# AD_2.net
KiCad netlist of a schematic drawn in Altium Designer
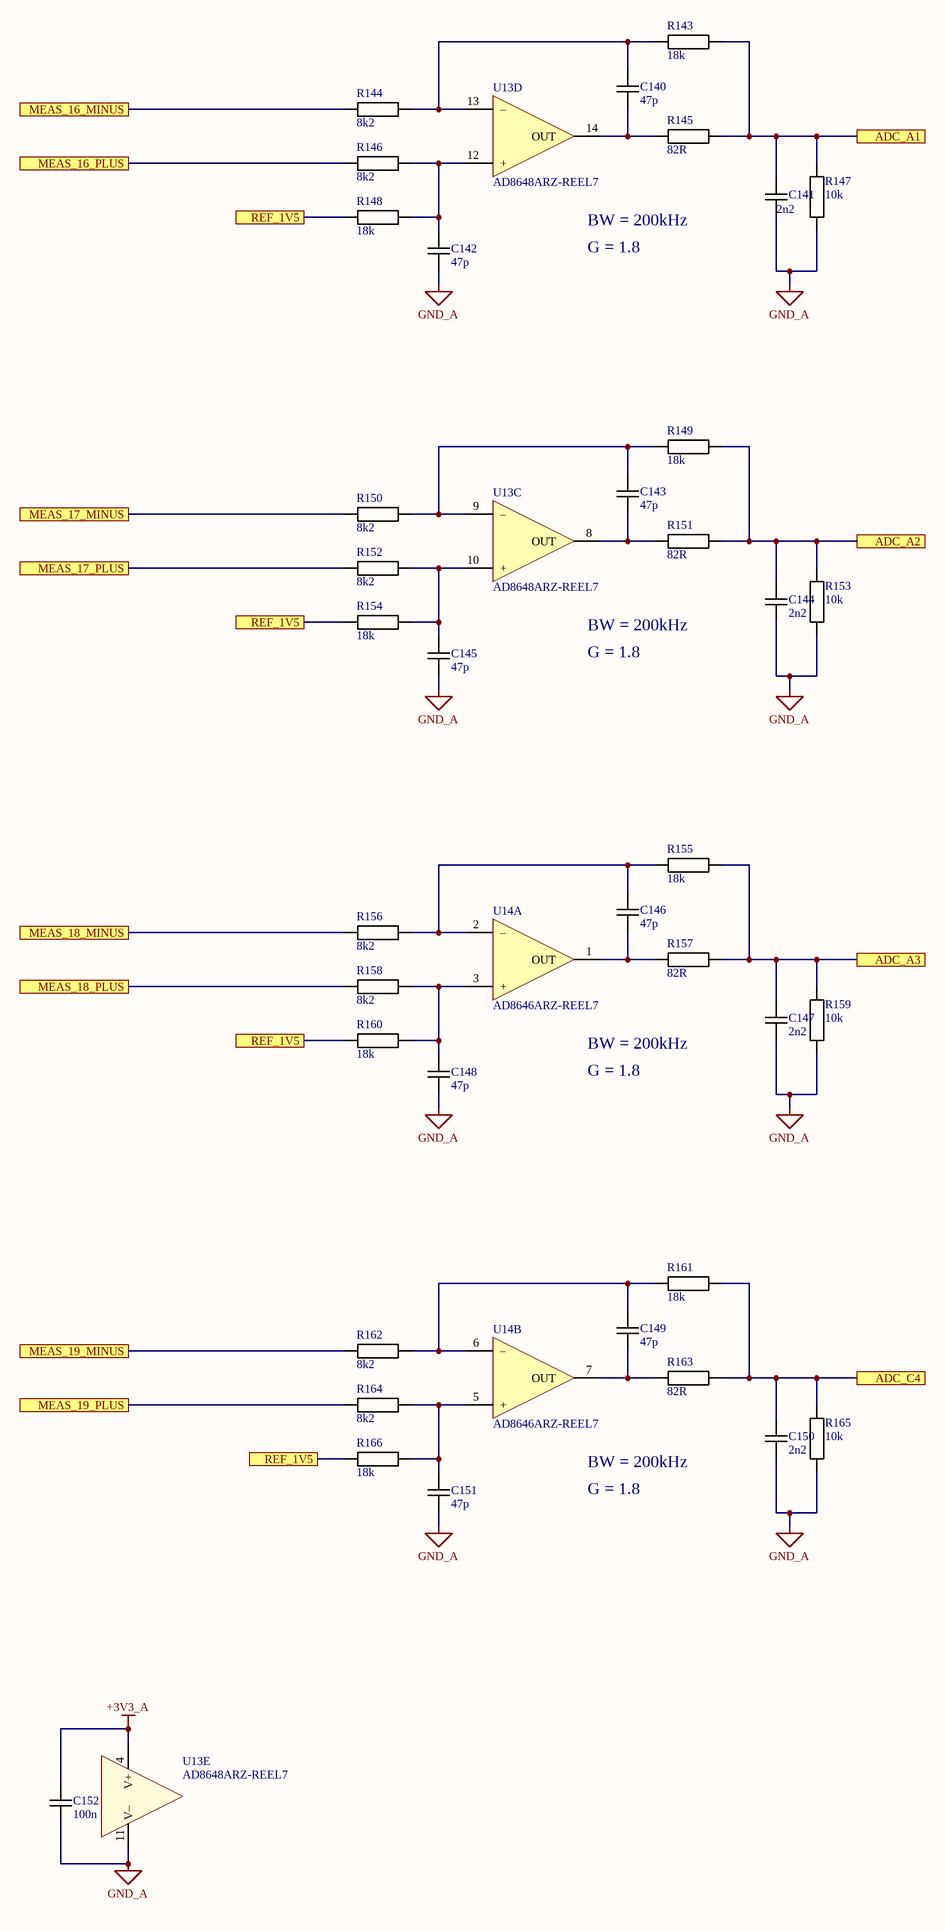
[diagram p0: AD_2.SchDoc]

(export (version "E")
  (design (tool "Eeschema 10.0.6"))
  (components
    (comp (ref "C140")
      (value "47p")
      (footprint "CAPACITOR 1608 REFLOW")
      (description "Capacitor X7R 10% 50V 1608(0603)")
      (libsource (lib "Capacitor") (part "Capacitor"))
    )
    (comp (ref "C141")
      (value "2n2")
      (footprint "CAPACITOR 1608 REFLOW")
      (description "Capacitor X7R 10% 50V 1608(0603)")
      (libsource (lib "Capacitor") (part "Capacitor"))
    )
    (comp (ref "C142")
      (value "47p")
      (footprint "CAPACITOR 1608 REFLOW")
      (description "Capacitor X7R 10% 50V 1608(0603)")
      (libsource (lib "Capacitor") (part "Capacitor"))
    )
    (comp (ref "C143")
      (value "47p")
      (footprint "CAPACITOR 1608 REFLOW")
      (description "Capacitor X7R 10% 50V 1608(0603)")
      (libsource (lib "Capacitor") (part "Capacitor"))
    )
    (comp (ref "C144")
      (value "2n2")
      (footprint "CAPACITOR 1608 REFLOW")
      (description "Capacitor X7R 10% 50V 1608(0603)")
      (libsource (lib "Capacitor") (part "Capacitor"))
    )
    (comp (ref "C145")
      (value "47p")
      (footprint "CAPACITOR 1608 REFLOW")
      (description "Capacitor X7R 10% 50V 1608(0603)")
      (libsource (lib "Capacitor") (part "Capacitor"))
    )
    (comp (ref "C146")
      (value "47p")
      (footprint "CAPACITOR 1608 REFLOW")
      (description "Capacitor X7R 10% 50V 1608(0603)")
      (libsource (lib "Capacitor") (part "Capacitor"))
    )
    (comp (ref "C147")
      (value "2n2")
      (footprint "CAPACITOR 1608 REFLOW")
      (description "Capacitor X7R 10% 50V 1608(0603)")
      (libsource (lib "Capacitor") (part "Capacitor"))
    )
    (comp (ref "C148")
      (value "47p")
      (footprint "CAPACITOR 1608 REFLOW")
      (description "Capacitor X7R 10% 50V 1608(0603)")
      (libsource (lib "Capacitor") (part "Capacitor"))
    )
    (comp (ref "C149")
      (value "47p")
      (footprint "CAPACITOR 1608 REFLOW")
      (description "Capacitor X7R 10% 50V 1608(0603)")
      (libsource (lib "Capacitor") (part "Capacitor"))
    )
    (comp (ref "C150")
      (value "2n2")
      (footprint "CAPACITOR 1608 REFLOW")
      (description "Capacitor X7R 10% 50V 1608(0603)")
      (libsource (lib "Capacitor") (part "Capacitor"))
    )
    (comp (ref "C151")
      (value "47p")
      (footprint "CAPACITOR 1608 REFLOW")
      (description "Capacitor X7R 10% 50V 1608(0603)")
      (libsource (lib "Capacitor") (part "Capacitor"))
    )
    (comp (ref "C152")
      (value "100n")
      (footprint "CAPACITOR 1608 REFLOW")
      (description "Capacitor X7R 10% 50V 1608(0603)")
      (libsource (lib "Capacitor") (part "Capacitor"))
    )
    (comp (ref "R143")
      (value "18k")
      (footprint "RESISTOR 1608 REFLOW")
      (description "Resistor 1% 50V 100mW 1608(0603)")
      (libsource (lib "Resistor") (part "Resistor"))
    )
    (comp (ref "R144")
      (value "8k2")
      (footprint "RESISTOR 1608 REFLOW")
      (description "Resistor 1% 50V 100mW 1608(0603)")
      (libsource (lib "Resistor") (part "Resistor"))
    )
    (comp (ref "R145")
      (value "82R")
      (footprint "RESISTOR 1608 REFLOW")
      (description "Resistor 1% 50V 100mW 1608(0603)")
      (libsource (lib "Resistor") (part "Resistor"))
    )
    (comp (ref "R146")
      (value "8k2")
      (footprint "RESISTOR 1608 REFLOW")
      (description "Resistor 1% 50V 100mW 1608(0603)")
      (libsource (lib "Resistor") (part "Resistor"))
    )
    (comp (ref "R147")
      (value "10k")
      (footprint "RESISTOR 1608 REFLOW")
      (description "Resistor 1% 50V 100mW 1608(0603)")
      (libsource (lib "Resistor") (part "Resistor"))
    )
    (comp (ref "R148")
      (value "18k")
      (footprint "RESISTOR 1608 REFLOW")
      (description "Resistor 1% 50V 100mW 1608(0603)")
      (libsource (lib "Resistor") (part "Resistor"))
    )
    (comp (ref "R149")
      (value "18k")
      (footprint "RESISTOR 1608 REFLOW")
      (description "Resistor 1% 50V 100mW 1608(0603)")
      (libsource (lib "Resistor") (part "Resistor"))
    )
    (comp (ref "R150")
      (value "8k2")
      (footprint "RESISTOR 1608 REFLOW")
      (description "Resistor 1% 50V 100mW 1608(0603)")
      (libsource (lib "Resistor") (part "Resistor"))
    )
    (comp (ref "R151")
      (value "82R")
      (footprint "RESISTOR 1608 REFLOW")
      (description "Resistor 1% 50V 100mW 1608(0603)")
      (libsource (lib "Resistor") (part "Resistor"))
    )
    (comp (ref "R152")
      (value "8k2")
      (footprint "RESISTOR 1608 REFLOW")
      (description "Resistor 1% 50V 100mW 1608(0603)")
      (libsource (lib "Resistor") (part "Resistor"))
    )
    (comp (ref "R153")
      (value "10k")
      (footprint "RESISTOR 1608 REFLOW")
      (description "Resistor 1% 50V 100mW 1608(0603)")
      (libsource (lib "Resistor") (part "Resistor"))
    )
    (comp (ref "R154")
      (value "18k")
      (footprint "RESISTOR 1608 REFLOW")
      (description "Resistor 1% 50V 100mW 1608(0603)")
      (libsource (lib "Resistor") (part "Resistor"))
    )
    (comp (ref "R155")
      (value "18k")
      (footprint "RESISTOR 1608 REFLOW")
      (description "Resistor 1% 50V 100mW 1608(0603)")
      (libsource (lib "Resistor") (part "Resistor"))
    )
    (comp (ref "R156")
      (value "8k2")
      (footprint "RESISTOR 1608 REFLOW")
      (description "Resistor 1% 50V 100mW 1608(0603)")
      (libsource (lib "Resistor") (part "Resistor"))
    )
    (comp (ref "R157")
      (value "82R")
      (footprint "RESISTOR 1608 REFLOW")
      (description "Resistor 1% 50V 100mW 1608(0603)")
      (libsource (lib "Resistor") (part "Resistor"))
    )
    (comp (ref "R158")
      (value "8k2")
      (footprint "RESISTOR 1608 REFLOW")
      (description "Resistor 1% 50V 100mW 1608(0603)")
      (libsource (lib "Resistor") (part "Resistor"))
    )
    (comp (ref "R159")
      (value "10k")
      (footprint "RESISTOR 1608 REFLOW")
      (description "Resistor 1% 50V 100mW 1608(0603)")
      (libsource (lib "Resistor") (part "Resistor"))
    )
    (comp (ref "R160")
      (value "18k")
      (footprint "RESISTOR 1608 REFLOW")
      (description "Resistor 1% 50V 100mW 1608(0603)")
      (libsource (lib "Resistor") (part "Resistor"))
    )
    (comp (ref "R161")
      (value "18k")
      (footprint "RESISTOR 1608 REFLOW")
      (description "Resistor 1% 50V 100mW 1608(0603)")
      (libsource (lib "Resistor") (part "Resistor"))
    )
    (comp (ref "R162")
      (value "8k2")
      (footprint "RESISTOR 1608 REFLOW")
      (description "Resistor 1% 50V 100mW 1608(0603)")
      (libsource (lib "Resistor") (part "Resistor"))
    )
    (comp (ref "R163")
      (value "82R")
      (footprint "RESISTOR 1608 REFLOW")
      (description "Resistor 1% 50V 100mW 1608(0603)")
      (libsource (lib "Resistor") (part "Resistor"))
    )
    (comp (ref "R164")
      (value "8k2")
      (footprint "RESISTOR 1608 REFLOW")
      (description "Resistor 1% 50V 100mW 1608(0603)")
      (libsource (lib "Resistor") (part "Resistor"))
    )
    (comp (ref "R165")
      (value "10k")
      (footprint "RESISTOR 1608 REFLOW")
      (description "Resistor 1% 50V 100mW 1608(0603)")
      (libsource (lib "Resistor") (part "Resistor"))
    )
    (comp (ref "R166")
      (value "18k")
      (footprint "RESISTOR 1608 REFLOW")
      (description "Resistor 1% 50V 100mW 1608(0603)")
      (libsource (lib "Resistor") (part "Resistor"))
    )
    (comp (ref "U13")
      (value "AD8648ARZ-REEL7")
      (footprint "SO14 P1.27 C4.0X8.8 H1.75")
      (description "Generic quad OPA 14 pins")
      (fields (field (name "MANUFACTURER") "Analog Device"))
      (libsource (lib "Amplifier") (part "OPA QUAD"))
    )
    (comp (ref "U14")
      (value "AD8646ARZ-REEL7")
      (footprint "SO8 P1.27 C4.0X5.0 H1.75")
      (description "Generic dual OPA 8 pins")
      (fields (field (name "MANUFACTURER") "Analog Devices"))
      (libsource (lib "Amplifier") (part "OPA DUAL"))
    )
  )
  (nets
    (net (code "1") (name "+3V3_A") (class "Default")
      (node (ref "C152") (pin "2") (pinfunction "2_2") (pintype "passive"))
      (node (ref "U13") (pin "4") (pinfunction "V+_4") (pintype "passive"))
    )
    (net (code "2") (name "/ADC_A1") (class "Default")
      (node (ref "C141") (pin "2") (pinfunction "2_2") (pintype "passive"))
      (node (ref "R143") (pin "2") (pinfunction "2_2") (pintype "passive"))
      (node (ref "R145") (pin "2") (pinfunction "2_2") (pintype "passive"))
      (node (ref "R147") (pin "1") (pinfunction "1_1") (pintype "passive"))
    )
    (net (code "3") (name "/ADC_A2") (class "Default")
      (node (ref "C144") (pin "2") (pinfunction "2_2") (pintype "passive"))
      (node (ref "R149") (pin "2") (pinfunction "2_2") (pintype "passive"))
      (node (ref "R151") (pin "2") (pinfunction "2_2") (pintype "passive"))
      (node (ref "R153") (pin "1") (pinfunction "1_1") (pintype "passive"))
    )
    (net (code "4") (name "/ADC_A3") (class "Default")
      (node (ref "C147") (pin "2") (pinfunction "2_2") (pintype "passive"))
      (node (ref "R155") (pin "2") (pinfunction "2_2") (pintype "passive"))
      (node (ref "R157") (pin "2") (pinfunction "2_2") (pintype "passive"))
      (node (ref "R159") (pin "1") (pinfunction "1_1") (pintype "passive"))
    )
    (net (code "5") (name "/ADC_C4") (class "Default")
      (node (ref "C150") (pin "2") (pinfunction "2_2") (pintype "passive"))
      (node (ref "R161") (pin "2") (pinfunction "2_2") (pintype "passive"))
      (node (ref "R163") (pin "2") (pinfunction "2_2") (pintype "passive"))
      (node (ref "R165") (pin "1") (pinfunction "1_1") (pintype "passive"))
    )
    (net (code "6") (name "/MEAS_16_MINUS") (class "Default")
      (node (ref "R144") (pin "1") (pinfunction "1_1") (pintype "passive"))
    )
    (net (code "7") (name "/MEAS_16_PLUS") (class "Default")
      (node (ref "R146") (pin "1") (pinfunction "1_1") (pintype "passive"))
    )
    (net (code "8") (name "/MEAS_17_MINUS") (class "Default")
      (node (ref "R150") (pin "1") (pinfunction "1_1") (pintype "passive"))
    )
    (net (code "9") (name "/MEAS_17_PLUS") (class "Default")
      (node (ref "R152") (pin "1") (pinfunction "1_1") (pintype "passive"))
    )
    (net (code "10") (name "/MEAS_18_MINUS") (class "Default")
      (node (ref "R156") (pin "1") (pinfunction "1_1") (pintype "passive"))
    )
    (net (code "11") (name "/MEAS_18_PLUS") (class "Default")
      (node (ref "R158") (pin "1") (pinfunction "1_1") (pintype "passive"))
    )
    (net (code "12") (name "/MEAS_19_MINUS") (class "Default")
      (node (ref "R162") (pin "1") (pinfunction "1_1") (pintype "passive"))
    )
    (net (code "13") (name "/MEAS_19_PLUS") (class "Default")
      (node (ref "R164") (pin "1") (pinfunction "1_1") (pintype "passive"))
    )
    (net (code "14") (name "/REF_1V5") (class "Default")
      (node (ref "R148") (pin "2") (pinfunction "2_2") (pintype "passive"))
      (node (ref "R154") (pin "2") (pinfunction "2_2") (pintype "passive"))
      (node (ref "R160") (pin "2") (pinfunction "2_2") (pintype "passive"))
      (node (ref "R166") (pin "2") (pinfunction "2_2") (pintype "passive"))
    )
    (net (code "15") (name "GND_A") (class "Default")
      (node (ref "C141") (pin "1") (pinfunction "1_1") (pintype "passive"))
      (node (ref "C142") (pin "1") (pinfunction "1_1") (pintype "passive"))
      (node (ref "C144") (pin "1") (pinfunction "1_1") (pintype "passive"))
      (node (ref "C145") (pin "1") (pinfunction "1_1") (pintype "passive"))
      (node (ref "C147") (pin "1") (pinfunction "1_1") (pintype "passive"))
      (node (ref "C148") (pin "1") (pinfunction "1_1") (pintype "passive"))
      (node (ref "C150") (pin "1") (pinfunction "1_1") (pintype "passive"))
      (node (ref "C151") (pin "1") (pinfunction "1_1") (pintype "passive"))
      (node (ref "C152") (pin "1") (pinfunction "1_1") (pintype "passive"))
      (node (ref "R147") (pin "2") (pinfunction "2_2") (pintype "passive"))
      (node (ref "R153") (pin "2") (pinfunction "2_2") (pintype "passive"))
      (node (ref "R159") (pin "2") (pinfunction "2_2") (pintype "passive"))
      (node (ref "R165") (pin "2") (pinfunction "2_2") (pintype "passive"))
      (node (ref "U13") (pin "11") (pinfunction "V–_11") (pintype "passive"))
    )
    (net (code "16") (name "Net-(U13C-+)") (class "Default")
      (node (ref "C145") (pin "2") (pinfunction "2_2") (pintype "passive"))
      (node (ref "R152") (pin "2") (pinfunction "2_2") (pintype "passive"))
      (node (ref "R154") (pin "1") (pinfunction "1_1") (pintype "passive"))
      (node (ref "U13") (pin "10") (pinfunction "+_10") (pintype "passive"))
    )
    (net (code "17") (name "Net-(U13C-OUT)") (class "Default")
      (node (ref "C143") (pin "1") (pinfunction "1_1") (pintype "passive"))
      (node (ref "R151") (pin "1") (pinfunction "1_1") (pintype "passive"))
      (node (ref "U13") (pin "8") (pinfunction "OUT_8") (pintype "passive"))
    )
    (net (code "18") (name "Net-(U13C-–)") (class "Default")
      (node (ref "C143") (pin "2") (pinfunction "2_2") (pintype "passive"))
      (node (ref "R149") (pin "1") (pinfunction "1_1") (pintype "passive"))
      (node (ref "R150") (pin "2") (pinfunction "2_2") (pintype "passive"))
      (node (ref "U13") (pin "9") (pinfunction "–_9") (pintype "passive"))
    )
    (net (code "19") (name "Net-(U13D-+)") (class "Default")
      (node (ref "C142") (pin "2") (pinfunction "2_2") (pintype "passive"))
      (node (ref "R146") (pin "2") (pinfunction "2_2") (pintype "passive"))
      (node (ref "R148") (pin "1") (pinfunction "1_1") (pintype "passive"))
      (node (ref "U13") (pin "12") (pinfunction "+_12") (pintype "passive"))
    )
    (net (code "20") (name "Net-(U13D-OUT)") (class "Default")
      (node (ref "C140") (pin "1") (pinfunction "1_1") (pintype "passive"))
      (node (ref "R145") (pin "1") (pinfunction "1_1") (pintype "passive"))
      (node (ref "U13") (pin "14") (pinfunction "OUT_14") (pintype "passive"))
    )
    (net (code "21") (name "Net-(U13D-–)") (class "Default")
      (node (ref "C140") (pin "2") (pinfunction "2_2") (pintype "passive"))
      (node (ref "R143") (pin "1") (pinfunction "1_1") (pintype "passive"))
      (node (ref "R144") (pin "2") (pinfunction "2_2") (pintype "passive"))
      (node (ref "U13") (pin "13") (pinfunction "–_13") (pintype "passive"))
    )
    (net (code "22") (name "Net-(U14A-+)") (class "Default")
      (node (ref "C148") (pin "2") (pinfunction "2_2") (pintype "passive"))
      (node (ref "R158") (pin "2") (pinfunction "2_2") (pintype "passive"))
      (node (ref "R160") (pin "1") (pinfunction "1_1") (pintype "passive"))
      (node (ref "U14") (pin "3") (pinfunction "+_3") (pintype "passive"))
    )
    (net (code "23") (name "Net-(U14A-OUT)") (class "Default")
      (node (ref "C146") (pin "1") (pinfunction "1_1") (pintype "passive"))
      (node (ref "R157") (pin "1") (pinfunction "1_1") (pintype "passive"))
      (node (ref "U14") (pin "1") (pinfunction "OUT_1") (pintype "passive"))
    )
    (net (code "24") (name "Net-(U14A-–)") (class "Default")
      (node (ref "C146") (pin "2") (pinfunction "2_2") (pintype "passive"))
      (node (ref "R155") (pin "1") (pinfunction "1_1") (pintype "passive"))
      (node (ref "R156") (pin "2") (pinfunction "2_2") (pintype "passive"))
      (node (ref "U14") (pin "2") (pinfunction "–_2") (pintype "passive"))
    )
    (net (code "25") (name "Net-(U14B-+)") (class "Default")
      (node (ref "C151") (pin "2") (pinfunction "2_2") (pintype "passive"))
      (node (ref "R164") (pin "2") (pinfunction "2_2") (pintype "passive"))
      (node (ref "R166") (pin "1") (pinfunction "1_1") (pintype "passive"))
      (node (ref "U14") (pin "5") (pinfunction "+_5") (pintype "passive"))
    )
    (net (code "26") (name "Net-(U14B-OUT)") (class "Default")
      (node (ref "C149") (pin "1") (pinfunction "1_1") (pintype "passive"))
      (node (ref "R163") (pin "1") (pinfunction "1_1") (pintype "passive"))
      (node (ref "U14") (pin "7") (pinfunction "OUT_7") (pintype "passive"))
    )
    (net (code "27") (name "Net-(U14B-–)") (class "Default")
      (node (ref "C149") (pin "2") (pinfunction "2_2") (pintype "passive"))
      (node (ref "R161") (pin "1") (pinfunction "1_1") (pintype "passive"))
      (node (ref "R162") (pin "2") (pinfunction "2_2") (pintype "passive"))
      (node (ref "U14") (pin "6") (pinfunction "–_6") (pintype "passive"))
    )
  )
)
